# MGNGSQ4_DC_Loopback.net
KiCad netlist of a schematic drawn in Altium Designer
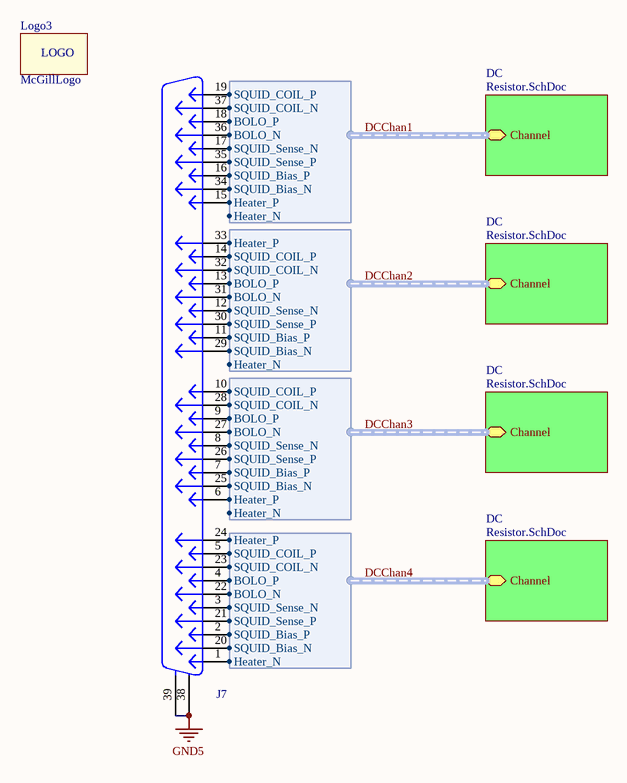
[diagram p0: MGNGSQ4_DC_Loopback.SchDoc]

(export (version "E")
  (design (tool "Eeschema 10.0.6"))
  (components
    (comp (ref "J7")
      (value "DB37M")
      (footprint "DSUB37-M")
      (fields
        (field (name "MANUFACTURER") "Norcomp")
        (field (name "MANUFACTURER PART NUMBER") "182-037-113R531")
      )
      (libsource (lib "MGNGSQ4_Dongles") (part "DB37M"))
    )
    (comp (ref "Logo3")
      (value "McGillLogo")
      (footprint "McGillLogo1")
      (description "Silkscreen Logo")
      (fields (field (name "MANUFACTURER") "McGill"))
      (libsource (lib "MGMEZZ04_Loopback") (part "Logo"))
    )
  )
  (nets
    (net (code "9") (name "GND5") (class "Default")
      (node (ref "J7") (pin "38") (pinfunction "MH1_38") (pintype "passive"))
      (node (ref "J7") (pin "39") (pinfunction "MH2_39") (pintype "passive"))
    )
    (net (code "10") (name "unconnected-(J7-Pad1)") (class "Default")
      (node (ref "J7") (pin "1") (pinfunction "1_1") (pintype "passive"))
    )
    (net (code "11") (name "unconnected-(J7-Pad2)") (class "Default")
      (node (ref "J7") (pin "2") (pinfunction "2_2") (pintype "passive"))
    )
    (net (code "12") (name "unconnected-(J7-Pad3)") (class "Default")
      (node (ref "J7") (pin "3") (pinfunction "3_3") (pintype "passive"))
    )
    (net (code "13") (name "unconnected-(J7-Pad4)") (class "Default")
      (node (ref "J7") (pin "4") (pinfunction "4_4") (pintype "passive"))
    )
    (net (code "14") (name "unconnected-(J7-Pad5)") (class "Default")
      (node (ref "J7") (pin "5") (pinfunction "5_5") (pintype "passive"))
    )
    (net (code "15") (name "unconnected-(J7-Pad6)") (class "Default")
      (node (ref "J7") (pin "6") (pinfunction "6_6") (pintype "passive"))
    )
    (net (code "16") (name "unconnected-(J7-Pad7)") (class "Default")
      (node (ref "J7") (pin "7") (pinfunction "7_7") (pintype "passive"))
    )
    (net (code "17") (name "unconnected-(J7-Pad8)") (class "Default")
      (node (ref "J7") (pin "8") (pinfunction "8_8") (pintype "passive"))
    )
    (net (code "18") (name "unconnected-(J7-Pad9)") (class "Default")
      (node (ref "J7") (pin "9") (pinfunction "9_9") (pintype "passive"))
    )
    (net (code "19") (name "unconnected-(J7-Pad10)") (class "Default")
      (node (ref "J7") (pin "10") (pinfunction "10_10") (pintype "passive"))
    )
    (net (code "20") (name "unconnected-(J7-Pad11)") (class "Default")
      (node (ref "J7") (pin "11") (pinfunction "11_11") (pintype "passive"))
    )
    (net (code "21") (name "unconnected-(J7-Pad12)") (class "Default")
      (node (ref "J7") (pin "12") (pinfunction "12_12") (pintype "passive"))
    )
    (net (code "22") (name "unconnected-(J7-Pad13)") (class "Default")
      (node (ref "J7") (pin "13") (pinfunction "13_13") (pintype "passive"))
    )
    (net (code "23") (name "unconnected-(J7-Pad14)") (class "Default")
      (node (ref "J7") (pin "14") (pinfunction "14_14") (pintype "passive"))
    )
    (net (code "24") (name "unconnected-(J7-Pad15)") (class "Default")
      (node (ref "J7") (pin "15") (pinfunction "15_15") (pintype "passive"))
    )
    (net (code "25") (name "unconnected-(J7-Pad16)") (class "Default")
      (node (ref "J7") (pin "16") (pinfunction "16_16") (pintype "passive"))
    )
    (net (code "26") (name "unconnected-(J7-Pad17)") (class "Default")
      (node (ref "J7") (pin "17") (pinfunction "17_17") (pintype "passive"))
    )
    (net (code "27") (name "unconnected-(J7-Pad18)") (class "Default")
      (node (ref "J7") (pin "18") (pinfunction "18_18") (pintype "passive"))
    )
    (net (code "28") (name "unconnected-(J7-Pad19)") (class "Default")
      (node (ref "J7") (pin "19") (pinfunction "19_19") (pintype "passive"))
    )
    (net (code "29") (name "unconnected-(J7-Pad20)") (class "Default")
      (node (ref "J7") (pin "20") (pinfunction "20_20") (pintype "passive"))
    )
    (net (code "30") (name "unconnected-(J7-Pad21)") (class "Default")
      (node (ref "J7") (pin "21") (pinfunction "21_21") (pintype "passive"))
    )
    (net (code "31") (name "unconnected-(J7-Pad22)") (class "Default")
      (node (ref "J7") (pin "22") (pinfunction "22_22") (pintype "passive"))
    )
    (net (code "32") (name "unconnected-(J7-Pad23)") (class "Default")
      (node (ref "J7") (pin "23") (pinfunction "23_23") (pintype "passive"))
    )
    (net (code "33") (name "unconnected-(J7-Pad24)") (class "Default")
      (node (ref "J7") (pin "24") (pinfunction "24_24") (pintype "passive"))
    )
    (net (code "34") (name "unconnected-(J7-Pad25)") (class "Default")
      (node (ref "J7") (pin "25") (pinfunction "25_25") (pintype "passive"))
    )
    (net (code "35") (name "unconnected-(J7-Pad26)") (class "Default")
      (node (ref "J7") (pin "26") (pinfunction "26_26") (pintype "passive"))
    )
    (net (code "36") (name "unconnected-(J7-Pad27)") (class "Default")
      (node (ref "J7") (pin "27") (pinfunction "27_27") (pintype "passive"))
    )
    (net (code "37") (name "unconnected-(J7-Pad28)") (class "Default")
      (node (ref "J7") (pin "28") (pinfunction "28_28") (pintype "passive"))
    )
    (net (code "38") (name "unconnected-(J7-Pad29)") (class "Default")
      (node (ref "J7") (pin "29") (pinfunction "29_29") (pintype "passive"))
    )
    (net (code "39") (name "unconnected-(J7-Pad30)") (class "Default")
      (node (ref "J7") (pin "30") (pinfunction "30_30") (pintype "passive"))
    )
    (net (code "40") (name "unconnected-(J7-Pad31)") (class "Default")
      (node (ref "J7") (pin "31") (pinfunction "31_31") (pintype "passive"))
    )
    (net (code "41") (name "unconnected-(J7-Pad32)") (class "Default")
      (node (ref "J7") (pin "32") (pinfunction "32_32") (pintype "passive"))
    )
    (net (code "42") (name "unconnected-(J7-Pad33)") (class "Default")
      (node (ref "J7") (pin "33") (pinfunction "33_33") (pintype "passive"))
    )
    (net (code "43") (name "unconnected-(J7-Pad34)") (class "Default")
      (node (ref "J7") (pin "34") (pinfunction "34_34") (pintype "passive"))
    )
    (net (code "44") (name "unconnected-(J7-Pad35)") (class "Default")
      (node (ref "J7") (pin "35") (pinfunction "35_35") (pintype "passive"))
    )
    (net (code "45") (name "unconnected-(J7-Pad36)") (class "Default")
      (node (ref "J7") (pin "36") (pinfunction "36_36") (pintype "passive"))
    )
    (net (code "46") (name "unconnected-(J7-Pad37)") (class "Default")
      (node (ref "J7") (pin "37") (pinfunction "37_37") (pintype "passive"))
    )
  )
)
